# Schematic.net
KiCad netlist of a schematic drawn in Altium Designer
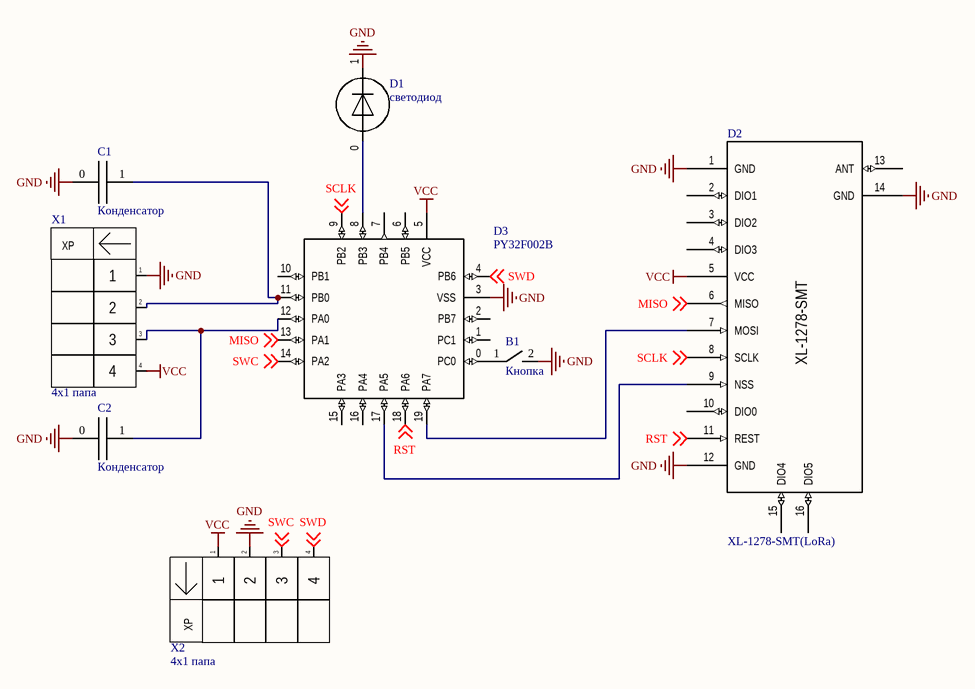
[diagram p0: Schematic.SchDoc]

(export (version "E")
  (design (tool "Eeschema 10.0.6"))
  (components
    (comp (ref "B1") (value "Кнопка") (footprint "Button") (libsource (lib "gost_lib") (part "Кнопка")))
    (comp (ref "C1")
      (value "Конденсатор")
      (footprint "0603 cap")
      (libsource (lib "gost_lib") (part "Конденсатор"))
    )
    (comp (ref "C2")
      (value "Конденсатор")
      (footprint "0603 cap")
      (libsource (lib "gost_lib") (part "Конденсатор"))
    )
    (comp (ref "D1")
      (value "светодиод")
      (footprint "0402 res")
      (libsource (lib "gost_lib") (part "светодиод"))
    )
    (comp (ref "D2")
      (value "XL-1278-SMT(LoRa)")
      (footprint "SX1278_V1.2")
      (description "Радиомодуль")
      (libsource (lib "gost_lib") (part "XL-1278-SMT(LoRa)"))
    )
    (comp (ref "D3")
      (value "PY32F002B")
      (footprint "TSSOP20")
      (description "МК")
      (libsource (lib "gost_lib") (part "PY32F002B"))
    )
    (comp (ref "X1")
      (value "4х1 папа")
      (footprint "NEMA17 разъём")
      (description "Разъём")
      (libsource (lib "gost_lib") (part "4х1 папа"))
    )
    (comp (ref "X2")
      (value "4х1 папа")
      (footprint "NEMA17 разъём")
      (description "Разъём")
      (libsource (lib "") (part "4х1 папа_1"))
    )
  )
  (nets
    (net (code "1") (name "GND") (class "Default")
      (node (ref "B1") (pin "2") (pinfunction "5_2") (pintype "passive"))
      (node (ref "C1") (pin "0") (pintype "passive"))
      (node (ref "C2") (pin "0") (pintype "passive"))
      (node (ref "D1") (pin "1") (pinfunction "3_1") (pintype "passive"))
      (node (ref "D2") (pin "1") (pinfunction "GND_1") (pintype "power_in"))
      (node (ref "D2") (pin "12") (pinfunction "GND_12") (pintype "power_in"))
      (node (ref "D2") (pin "14") (pinfunction "GND_14") (pintype "power_in"))
      (node (ref "D3") (pin "3") (pinfunction "VSS_3") (pintype "power_in"))
      (node (ref "X1") (pin "1") (pinfunction "1_1") (pintype "passive"))
      (node (ref "X2") (pin "2") (pinfunction "2_2") (pintype "passive"))
    )
    (net (code "2") (name "MISO") (class "Default")
      (node (ref "D2") (pin "6") (pinfunction "MISO_6") (pintype "output"))
      (node (ref "D3") (pin "13") (pinfunction "PA1_13") (pintype "bidirectional"))
    )
    (net (code "3") (name "Net-(B1-4)") (class "Default")
      (node (ref "B1") (pin "1") (pinfunction "4_1") (pintype "passive"))
      (node (ref "D3") (pin "0") (pinfunction "PC0_0") (pintype "bidirectional"))
    )
    (net (code "4") (name "Net-(D1-2)") (class "Default")
      (node (ref "D1") (pin "0") (pinfunction "2_0") (pintype "passive"))
      (node (ref "D3") (pin "8") (pinfunction "PB3_8") (pintype "bidirectional"))
    )
    (net (code "5") (name "Net-(D2-MOSI)") (class "Default")
      (node (ref "D2") (pin "7") (pinfunction "MOSI_7") (pintype "input"))
      (node (ref "D3") (pin "19") (pinfunction "PA7_19") (pintype "bidirectional"))
    )
    (net (code "6") (name "Net-(D2-NSS)") (class "Default")
      (node (ref "D2") (pin "9") (pinfunction "NSS_9") (pintype "input"))
      (node (ref "D3") (pin "17") (pinfunction "PA5_17") (pintype "bidirectional"))
    )
    (net (code "7") (name "Net-(D3-PA0)") (class "Default")
      (node (ref "C2") (pin "1") (pintype "passive"))
      (node (ref "D3") (pin "12") (pinfunction "PA0_12") (pintype "bidirectional"))
      (node (ref "X1") (pin "3") (pinfunction "3_3") (pintype "passive"))
    )
    (net (code "8") (name "Net-(D3-PB0)") (class "Default")
      (node (ref "C1") (pin "1") (pintype "passive"))
      (node (ref "D3") (pin "11") (pinfunction "PB0_11") (pintype "bidirectional"))
      (node (ref "X1") (pin "2") (pinfunction "2_2") (pintype "passive"))
    )
    (net (code "9") (name "RST") (class "Default")
      (node (ref "D2") (pin "11") (pinfunction "REST_11") (pintype "input"))
      (node (ref "D3") (pin "18") (pinfunction "PA6_18") (pintype "bidirectional"))
    )
    (net (code "10") (name "SCLK") (class "Default")
      (node (ref "D2") (pin "8") (pinfunction "SCLK_8") (pintype "input"))
      (node (ref "D3") (pin "9") (pinfunction "PB2_9") (pintype "bidirectional"))
    )
    (net (code "11") (name "SWC") (class "Default")
      (node (ref "D3") (pin "14") (pinfunction "PA2_14") (pintype "bidirectional"))
      (node (ref "X2") (pin "3") (pinfunction "3_3") (pintype "passive"))
    )
    (net (code "12") (name "SWD") (class "Default")
      (node (ref "D3") (pin "4") (pinfunction "PB6_4") (pintype "bidirectional"))
      (node (ref "X2") (pin "4") (pinfunction "4_4") (pintype "passive"))
    )
    (net (code "13") (name "VCC") (class "Default")
      (node (ref "D2") (pin "5") (pinfunction "VCC_5") (pintype "power_in"))
      (node (ref "D3") (pin "5") (pinfunction "VCC_5") (pintype "power_in"))
      (node (ref "X1") (pin "4") (pinfunction "4_4") (pintype "passive"))
      (node (ref "X2") (pin "1") (pinfunction "1_1") (pintype "passive"))
    )
    (net (code "14") (name "unconnected-(D2-ANT-Pad13)") (class "Default")
      (node (ref "D2") (pin "13") (pinfunction "ANT_13") (pintype "bidirectional"))
    )
    (net (code "15") (name "unconnected-(D2-DIO0-Pad10)") (class "Default")
      (node (ref "D2") (pin "10") (pinfunction "DIO0_10") (pintype "bidirectional"))
    )
    (net (code "16") (name "unconnected-(D2-DIO1-Pad2)") (class "Default")
      (node (ref "D2") (pin "2") (pinfunction "DIO1_2") (pintype "bidirectional"))
    )
    (net (code "17") (name "unconnected-(D2-DIO2-Pad3)") (class "Default")
      (node (ref "D2") (pin "3") (pinfunction "DIO2_3") (pintype "bidirectional"))
    )
    (net (code "18") (name "unconnected-(D2-DIO3-Pad4)") (class "Default")
      (node (ref "D2") (pin "4") (pinfunction "DIO3_4") (pintype "bidirectional"))
    )
    (net (code "19") (name "unconnected-(D2-DIO4-Pad15)") (class "Default")
      (node (ref "D2") (pin "15") (pinfunction "DIO4_15") (pintype "bidirectional"))
    )
    (net (code "20") (name "unconnected-(D2-DIO5-Pad16)") (class "Default")
      (node (ref "D2") (pin "16") (pinfunction "DIO5_16") (pintype "bidirectional"))
    )
    (net (code "21") (name "unconnected-(D3-PA3-Pad15)") (class "Default")
      (node (ref "D3") (pin "15") (pinfunction "PA3_15") (pintype "bidirectional"))
    )
    (net (code "22") (name "unconnected-(D3-PA4-Pad16)") (class "Default")
      (node (ref "D3") (pin "16") (pinfunction "PA4_16") (pintype "bidirectional"))
    )
    (net (code "23") (name "unconnected-(D3-PB1-Pad10)") (class "Default")
      (node (ref "D3") (pin "10") (pinfunction "PB1_10") (pintype "bidirectional"))
    )
    (net (code "24") (name "unconnected-(D3-PB4-Pad7)") (class "Default")
      (node (ref "D3") (pin "7") (pinfunction "PB4_7") (pintype "output"))
    )
    (net (code "25") (name "unconnected-(D3-PB5-Pad6)") (class "Default")
      (node (ref "D3") (pin "6") (pinfunction "PB5_6") (pintype "bidirectional"))
    )
    (net (code "26") (name "unconnected-(D3-PB7-Pad2)") (class "Default")
      (node (ref "D3") (pin "2") (pinfunction "PB7_2") (pintype "bidirectional"))
    )
    (net (code "27") (name "unconnected-(D3-PC1-Pad1)") (class "Default")
      (node (ref "D3") (pin "1") (pinfunction "PC1_1") (pintype "bidirectional"))
    )
  )
)
